# plugV11-to-pcbway-4.net
KiCad netlist of a schematic drawn in EAGLE
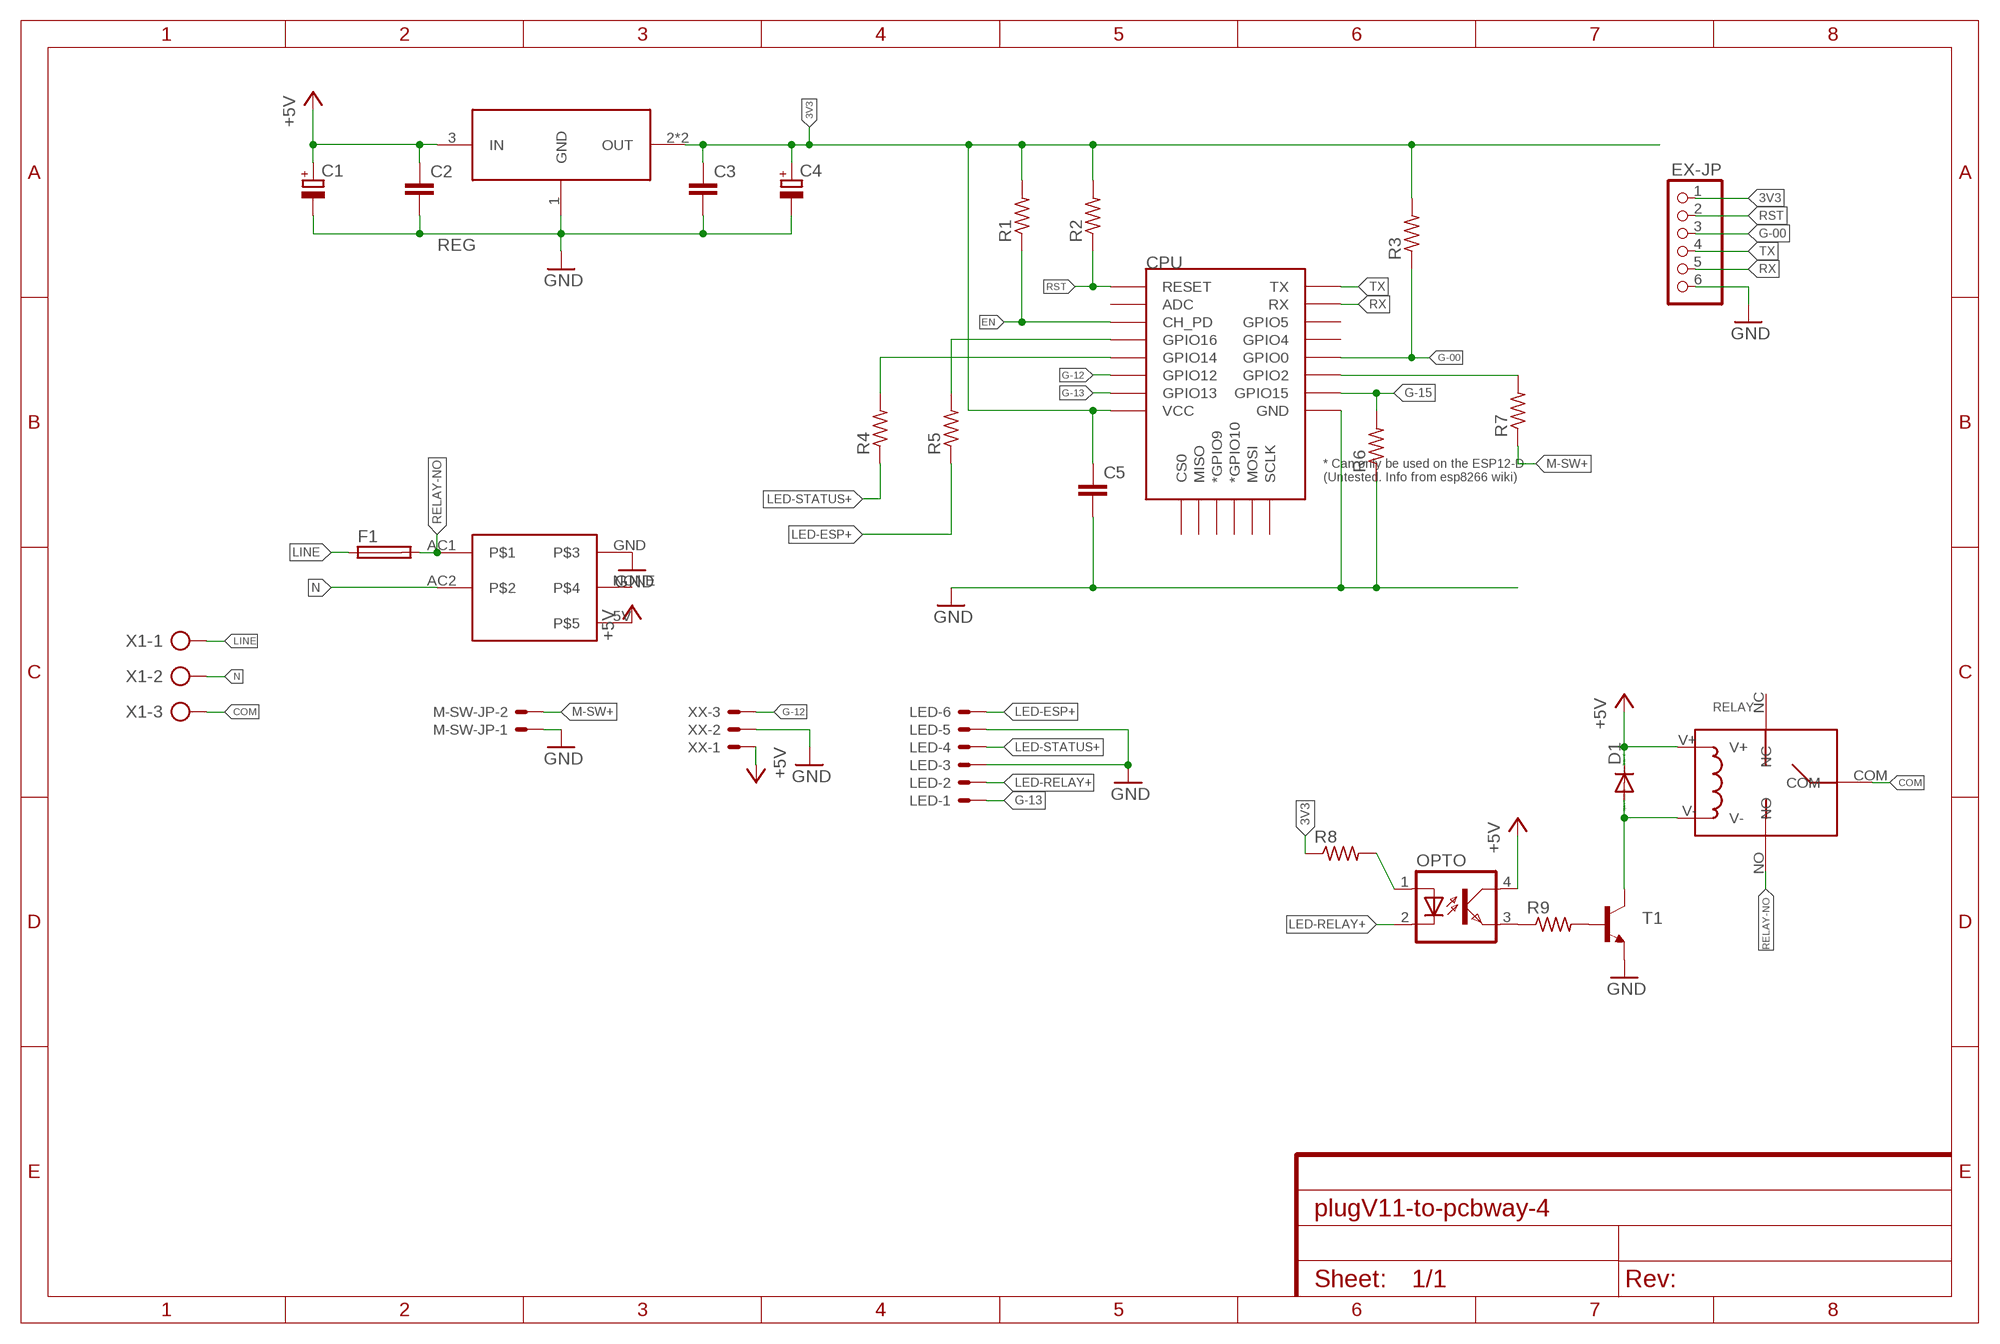
[diagram p0: schematic, sheet 1]

(export (version "E")
  (design (tool "Eeschema 10.0.6"))
  (components
    (comp (ref "C1")
      (value "CPOL-EUB/3528-21R")
      (footprint "eagle-import:B_3528-21R")
      (libsource (lib "eagle-import") (part "CPOL-EUB/3528-21R"))
    )
    (comp (ref "C2")
      (value "C-EUC0603K")
      (footprint "eagle-import:C0603K")
      (libsource (lib "eagle-import") (part "C-EUC0603K"))
    )
    (comp (ref "C3")
      (value "C-EUC0603K")
      (footprint "eagle-import:C0603K")
      (libsource (lib "eagle-import") (part "C-EUC0603K"))
    )
    (comp (ref "C4")
      (value "CPOL-EUB/3528-21R")
      (footprint "eagle-import:B_3528-21R")
      (libsource (lib "eagle-import") (part "CPOL-EUB/3528-21R"))
    )
    (comp (ref "C5")
      (value "C-EUC0805")
      (footprint "eagle-import:C0805")
      (libsource (lib "eagle-import") (part "C-EUC0805"))
    )
    (comp (ref "CPU")
      (value "ESP12ESMD")
      (footprint "eagle-import:ESP12E-SMD")
      (libsource (lib "eagle-import") (part "ESP12ESMD"))
    )
    (comp (ref "D1")
      (value "DIODE-DO-214AC")
      (footprint "eagle-import:DO-214AC")
      (libsource (lib "eagle-import") (part "DIODE-DO-214AC"))
    )
    (comp (ref "EX-JP")
      (value "PINHD-1X6")
      (footprint "eagle-import:1X06")
      (libsource (lib "eagle-import") (part "PINHD-1X6"))
    )
    (comp (ref "F1")
      (value "FUSESH22,5")
      (footprint "eagle-import:SH22,5")
      (libsource (lib "eagle-import") (part "FUSESH22,5"))
    )
    (comp (ref "LED")
      (value "53048-06")
      (footprint "eagle-import:53048-06")
      (fields (field (name "MF") "WALDOM/MOLEX") (field (name "MPN") "53048-0610"))
      (libsource (lib "eagle-import") (part "53?-06048"))
    )
    (comp (ref "M-SW-JP")
      (value "53048-02")
      (footprint "eagle-import:53048-02")
      (fields (field (name "MF") "MOLEX") (field (name "MPN") "53048-0210"))
      (libsource (lib "eagle-import") (part "53?-02048"))
    )
    (comp (ref "OPTO")
      (value "PC817")
      (footprint "eagle-import:DIL04")
      (fields (field (name "MPN") "PC817X4J000F"))
      (libsource (lib "eagle-import") (part "PC817"))
    )
    (comp (ref "R1")
      (value "R-US_R0603")
      (footprint "eagle-import:R0603")
      (libsource (lib "eagle-import") (part "R-US_R0603"))
    )
    (comp (ref "R2")
      (value "R-US_R0603")
      (footprint "eagle-import:R0603")
      (libsource (lib "eagle-import") (part "R-US_R0603"))
    )
    (comp (ref "R3")
      (value "R-US_R0603")
      (footprint "eagle-import:R0603")
      (libsource (lib "eagle-import") (part "R-US_R0603"))
    )
    (comp (ref "R4")
      (value "R-US_R0603")
      (footprint "eagle-import:R0603")
      (libsource (lib "eagle-import") (part "R-US_R0603"))
    )
    (comp (ref "R5")
      (value "R-US_R0603")
      (footprint "eagle-import:R0603")
      (libsource (lib "eagle-import") (part "R-US_R0603"))
    )
    (comp (ref "R6")
      (value "R-US_R0603")
      (footprint "eagle-import:R0603")
      (libsource (lib "eagle-import") (part "R-US_R0603"))
    )
    (comp (ref "R7")
      (value "R-US_R0603")
      (footprint "eagle-import:R0603")
      (libsource (lib "eagle-import") (part "R-US_R0603"))
    )
    (comp (ref "R8")
      (value "R-US_M0805")
      (footprint "eagle-import:M0805")
      (libsource (lib "eagle-import") (part "R-US_M0805"))
    )
    (comp (ref "R9")
      (value "R-US_M0805")
      (footprint "eagle-import:M0805")
      (libsource (lib "eagle-import") (part "R-US_M0805"))
    )
    (comp (ref "REG")
      (value "AMS1117-3.3")
      (footprint "eagle-import:SOT-223")
      (libsource (lib "eagle-import") (part "AMS1117-3.3"))
    )
    (comp (ref "RELAY")
      (value "RELAY-SONGLE")
      (footprint "eagle-import:RELAY-SONGLE")
      (libsource (lib "eagle-import") (part "RELAY-SONGLE"))
    )
    (comp (ref "T1")
      (value "BC817-NPN-SOT23-BEC")
      (footprint "eagle-import:SOT23-BEC")
      (libsource (lib "eagle-import") (part "-NPN-SOT23-BECBC817"))
    )
    (comp (ref "U$4")
      (value "POWERSUPPLY-5V-700MA")
      (footprint "eagle-import:POWERSUPPLY-5V-700MA")
      (libsource (lib "eagle-import") (part "POWERSUPPLY-5V-700MA"))
    )
    (comp (ref "X1")
      (value "AK300/3")
      (footprint "eagle-import:AK300_3")
      (libsource (lib "eagle-import") (part "AK300/3"))
    )
    (comp (ref "XX")
      (value "53048-03")
      (footprint "eagle-import:53048-03")
      (fields (field (name "MF") "WALDOM/MOLEX") (field (name "MPN") "53048-0310"))
      (libsource (lib "eagle-import") (part "53?-03048"))
    )
  )
  (nets
    (net (code "1") (name "+5V") (class "Default")
      (node (ref "C1") (pin "+") (pinfunction "+_+") (pintype "passive"))
      (node (ref "C2") (pin "1") (pinfunction "1_1") (pintype "passive"))
      (node (ref "D1") (pin "C") (pinfunction "C_C") (pintype "passive"))
      (node (ref "OPTO") (pin "4") (pinfunction "COL_4") (pintype "passive"))
      (node (ref "REG") (pin "3") (pinfunction "IN_3") (pintype "input"))
      (node (ref "RELAY") (pin "V+") (pinfunction "V+_V+") (pintype "bidirectional"))
      (node (ref "U$4") (pin "5V") (pinfunction "P$5_5V") (pintype "bidirectional"))
      (node (ref "XX") (pin "1") (pinfunction "S_1") (pintype "passive"))
    )
    (net (code "2") (name "3V3") (class "Default")
      (node (ref "C3") (pin "1") (pinfunction "1_1") (pintype "passive"))
      (node (ref "C4") (pin "+") (pinfunction "+_+") (pintype "passive"))
      (node (ref "C5") (pin "1") (pinfunction "1_1") (pintype "passive"))
      (node (ref "CPU") (pin "VCC") (pinfunction "VCC_VCC") (pintype "bidirectional"))
      (node (ref "EX-JP") (pin "1") (pinfunction "1_1") (pintype "passive"))
      (node (ref "R1") (pin "2") (pinfunction "2_2") (pintype "passive"))
      (node (ref "R2") (pin "2") (pinfunction "2_2") (pintype "passive"))
      (node (ref "R3") (pin "2") (pinfunction "2_2") (pintype "passive"))
      (node (ref "R8") (pin "1") (pinfunction "1_1") (pintype "passive"))
      (node (ref "REG") (pin "2") (pinfunction "OUT_2") (pintype "output"))
      (node (ref "REG") (pin "4") (pinfunction "OUT_4") (pintype "output"))
    )
    (net (code "3") (name "COM") (class "Default")
      (node (ref "RELAY") (pin "COM") (pinfunction "COM_COM") (pintype "bidirectional"))
      (node (ref "X1") (pin "3") (pinfunction "KL_3") (pintype "passive"))
    )
    (net (code "4") (name "EN") (class "Default")
      (node (ref "CPU") (pin "CH_PD") (pinfunction "CH_PD_CH_PD") (pintype "bidirectional"))
      (node (ref "R1") (pin "1") (pinfunction "1_1") (pintype "passive"))
    )
    (net (code "5") (name "G-00") (class "Default")
      (node (ref "CPU") (pin "GPIO0") (pinfunction "GPIO0_GPIO0") (pintype "bidirectional"))
      (node (ref "EX-JP") (pin "3") (pinfunction "3_3") (pintype "passive"))
      (node (ref "R3") (pin "1") (pinfunction "1_1") (pintype "passive"))
    )
    (net (code "6") (name "G-12") (class "Default")
      (node (ref "CPU") (pin "GPIO12") (pinfunction "GPIO12_GPIO12") (pintype "bidirectional"))
      (node (ref "XX") (pin "3") (pinfunction "S_3") (pintype "passive"))
    )
    (net (code "7") (name "G-13") (class "Default")
      (node (ref "CPU") (pin "GPIO13") (pinfunction "GPIO13_GPIO13") (pintype "bidirectional"))
      (node (ref "LED") (pin "1") (pinfunction "S_1") (pintype "passive"))
    )
    (net (code "8") (name "G-15") (class "Default")
      (node (ref "CPU") (pin "GPIO15") (pinfunction "GPIO15_GPIO15") (pintype "bidirectional"))
      (node (ref "R6") (pin "2") (pinfunction "2_2") (pintype "passive"))
    )
    (net (code "9") (name "GND") (class "Default")
      (node (ref "C1") (pin "-") (pinfunction "-_-") (pintype "passive"))
      (node (ref "C2") (pin "2") (pinfunction "2_2") (pintype "passive"))
      (node (ref "C3") (pin "2") (pinfunction "2_2") (pintype "passive"))
      (node (ref "C4") (pin "-") (pinfunction "-_-") (pintype "passive"))
      (node (ref "C5") (pin "2") (pinfunction "2_2") (pintype "passive"))
      (node (ref "CPU") (pin "GND") (pinfunction "GND_GND") (pintype "bidirectional"))
      (node (ref "EX-JP") (pin "6") (pinfunction "6_6") (pintype "passive"))
      (node (ref "LED") (pin "3") (pinfunction "S_3") (pintype "passive"))
      (node (ref "LED") (pin "5") (pinfunction "S_5") (pintype "passive"))
      (node (ref "M-SW-JP") (pin "1") (pinfunction "S_1") (pintype "passive"))
      (node (ref "R6") (pin "1") (pinfunction "1_1") (pintype "passive"))
      (node (ref "REG") (pin "1") (pinfunction "GND_1") (pintype "passive"))
      (node (ref "T1") (pin "E") (pinfunction "E_E") (pintype "passive"))
      (node (ref "U$4") (pin "GND") (pinfunction "P$3_GND") (pintype "bidirectional"))
      (node (ref "XX") (pin "2") (pinfunction "S_2") (pintype "passive"))
    )
    (net (code "10") (name "LED-ESP+") (class "Default")
      (node (ref "LED") (pin "6") (pinfunction "S_6") (pintype "passive"))
      (node (ref "R5") (pin "1") (pinfunction "1_1") (pintype "passive"))
    )
    (net (code "11") (name "LED-RELAY+") (class "Default")
      (node (ref "LED") (pin "2") (pinfunction "S_2") (pintype "passive"))
      (node (ref "OPTO") (pin "2") (pinfunction "C_2") (pintype "passive"))
    )
    (net (code "12") (name "LED-STATUS+") (class "Default")
      (node (ref "LED") (pin "4") (pinfunction "S_4") (pintype "passive"))
      (node (ref "R4") (pin "1") (pinfunction "1_1") (pintype "passive"))
    )
    (net (code "13") (name "LINE") (class "Default")
      (node (ref "F1") (pin "1") (pinfunction "1_1") (pintype "passive"))
      (node (ref "X1") (pin "1") (pinfunction "KL_1") (pintype "passive"))
    )
    (net (code "14") (name "M-SW+") (class "Default")
      (node (ref "M-SW-JP") (pin "2") (pinfunction "S_2") (pintype "passive"))
      (node (ref "R7") (pin "1") (pinfunction "1_1") (pintype "passive"))
    )
    (net (code "15") (name "N") (class "Default")
      (node (ref "U$4") (pin "AC2") (pinfunction "P$2_AC2") (pintype "bidirectional"))
      (node (ref "X1") (pin "2") (pinfunction "KL_2") (pintype "passive"))
    )
    (net (code "16") (name "Net-(CPU-PadGPIO2)") (class "Default")
      (node (ref "CPU") (pin "GPIO2") (pinfunction "GPIO2_GPIO2") (pintype "bidirectional"))
      (node (ref "R7") (pin "2") (pinfunction "2_2") (pintype "passive"))
    )
    (net (code "17") (name "Net-(CPU-PadGPIO14)") (class "Default")
      (node (ref "CPU") (pin "GPIO14") (pinfunction "GPIO14_GPIO14") (pintype "bidirectional"))
      (node (ref "R4") (pin "2") (pinfunction "2_2") (pintype "passive"))
    )
    (net (code "18") (name "Net-(CPU-PadGPIO16)") (class "Default")
      (node (ref "CPU") (pin "GPIO16") (pinfunction "GPIO16_GPIO16") (pintype "bidirectional"))
      (node (ref "R5") (pin "2") (pinfunction "2_2") (pintype "passive"))
    )
    (net (code "19") (name "Net-(D1-PadA)") (class "Default")
      (node (ref "D1") (pin "A") (pinfunction "A_A") (pintype "passive"))
      (node (ref "RELAY") (pin "V-") (pinfunction "V-_V-") (pintype "bidirectional"))
      (node (ref "T1") (pin "C") (pinfunction "C_C") (pintype "passive"))
    )
    (net (code "20") (name "Net-(OPTO-A)") (class "Default")
      (node (ref "OPTO") (pin "1") (pinfunction "A_1") (pintype "passive"))
      (node (ref "R8") (pin "2") (pinfunction "2_2") (pintype "passive"))
    )
    (net (code "21") (name "Net-(OPTO-EMIT)") (class "Default")
      (node (ref "OPTO") (pin "3") (pinfunction "EMIT_3") (pintype "passive"))
      (node (ref "R9") (pin "1") (pinfunction "1_1") (pintype "passive"))
    )
    (net (code "22") (name "Net-(R9-Pad2)") (class "Default")
      (node (ref "R9") (pin "2") (pinfunction "2_2") (pintype "passive"))
      (node (ref "T1") (pin "B") (pinfunction "B_B") (pintype "passive"))
    )
    (net (code "23") (name "RELAY-NO") (class "Default")
      (node (ref "F1") (pin "2") (pinfunction "2_2") (pintype "passive"))
      (node (ref "RELAY") (pin "NO") (pinfunction "NO_NO") (pintype "bidirectional"))
      (node (ref "U$4") (pin "AC1") (pinfunction "P$1_AC1") (pintype "bidirectional"))
    )
    (net (code "24") (name "RST") (class "Default")
      (node (ref "CPU") (pin "RESET") (pinfunction "RESET_RESET") (pintype "bidirectional"))
      (node (ref "EX-JP") (pin "2") (pinfunction "2_2") (pintype "passive"))
      (node (ref "R2") (pin "1") (pinfunction "1_1") (pintype "passive"))
    )
    (net (code "25") (name "RX") (class "Default")
      (node (ref "CPU") (pin "RXD0") (pinfunction "RX_RXD0") (pintype "bidirectional"))
      (node (ref "EX-JP") (pin "5") (pinfunction "5_5") (pintype "passive"))
    )
    (net (code "26") (name "TX") (class "Default")
      (node (ref "CPU") (pin "TXD0") (pinfunction "TX_TXD0") (pintype "bidirectional"))
      (node (ref "EX-JP") (pin "4") (pinfunction "4_4") (pintype "passive"))
    )
    (net (code "27") (name "unconnected-(CPU-*GPIO9-PadGPIO9)") (class "Default")
      (node (ref "CPU") (pin "GPIO9") (pinfunction "*GPIO9_GPIO9") (pintype "bidirectional"))
    )
    (net (code "28") (name "unconnected-(CPU-*GPIO10-PadGPIO10)") (class "Default")
      (node (ref "CPU") (pin "GPIO10") (pinfunction "*GPIO10_GPIO10") (pintype "bidirectional"))
    )
    (net (code "29") (name "unconnected-(CPU-PadADC)") (class "Default")
      (node (ref "CPU") (pin "ADC") (pinfunction "ADC_ADC") (pintype "bidirectional"))
    )
    (net (code "30") (name "unconnected-(CPU-PadCS0)") (class "Default")
      (node (ref "CPU") (pin "CS0") (pinfunction "CS0_CS0") (pintype "bidirectional"))
    )
    (net (code "31") (name "unconnected-(CPU-PadGPIO4)") (class "Default")
      (node (ref "CPU") (pin "GPIO4") (pinfunction "GPIO4_GPIO4") (pintype "bidirectional"))
    )
    (net (code "32") (name "unconnected-(CPU-PadGPIO5)") (class "Default")
      (node (ref "CPU") (pin "GPIO5") (pinfunction "GPIO5_GPIO5") (pintype "bidirectional"))
    )
    (net (code "33") (name "unconnected-(CPU-PadMISO)") (class "Default")
      (node (ref "CPU") (pin "MISO") (pinfunction "MISO_MISO") (pintype "bidirectional"))
    )
    (net (code "34") (name "unconnected-(CPU-PadMOSI)") (class "Default")
      (node (ref "CPU") (pin "MOSI") (pinfunction "MOSI_MOSI") (pintype "bidirectional"))
    )
    (net (code "35") (name "unconnected-(CPU-PadSCLK)") (class "Default")
      (node (ref "CPU") (pin "SCLK") (pinfunction "SCLK_SCLK") (pintype "bidirectional"))
    )
    (net (code "36") (name "unconnected-(RELAY-PadNC)") (class "Default")
      (node (ref "RELAY") (pin "NC") (pinfunction "NC_NC") (pintype "bidirectional"))
    )
    (net (code "37") (name "unconnected-(U$4-P$4-PadNONE)") (class "Default")
      (node (ref "U$4") (pin "NONE") (pinfunction "P$4_NONE") (pintype "bidirectional"))
    )
  )
)
